# H0BR41.net
KiCad netlist of a schematic drawn in EAGLE
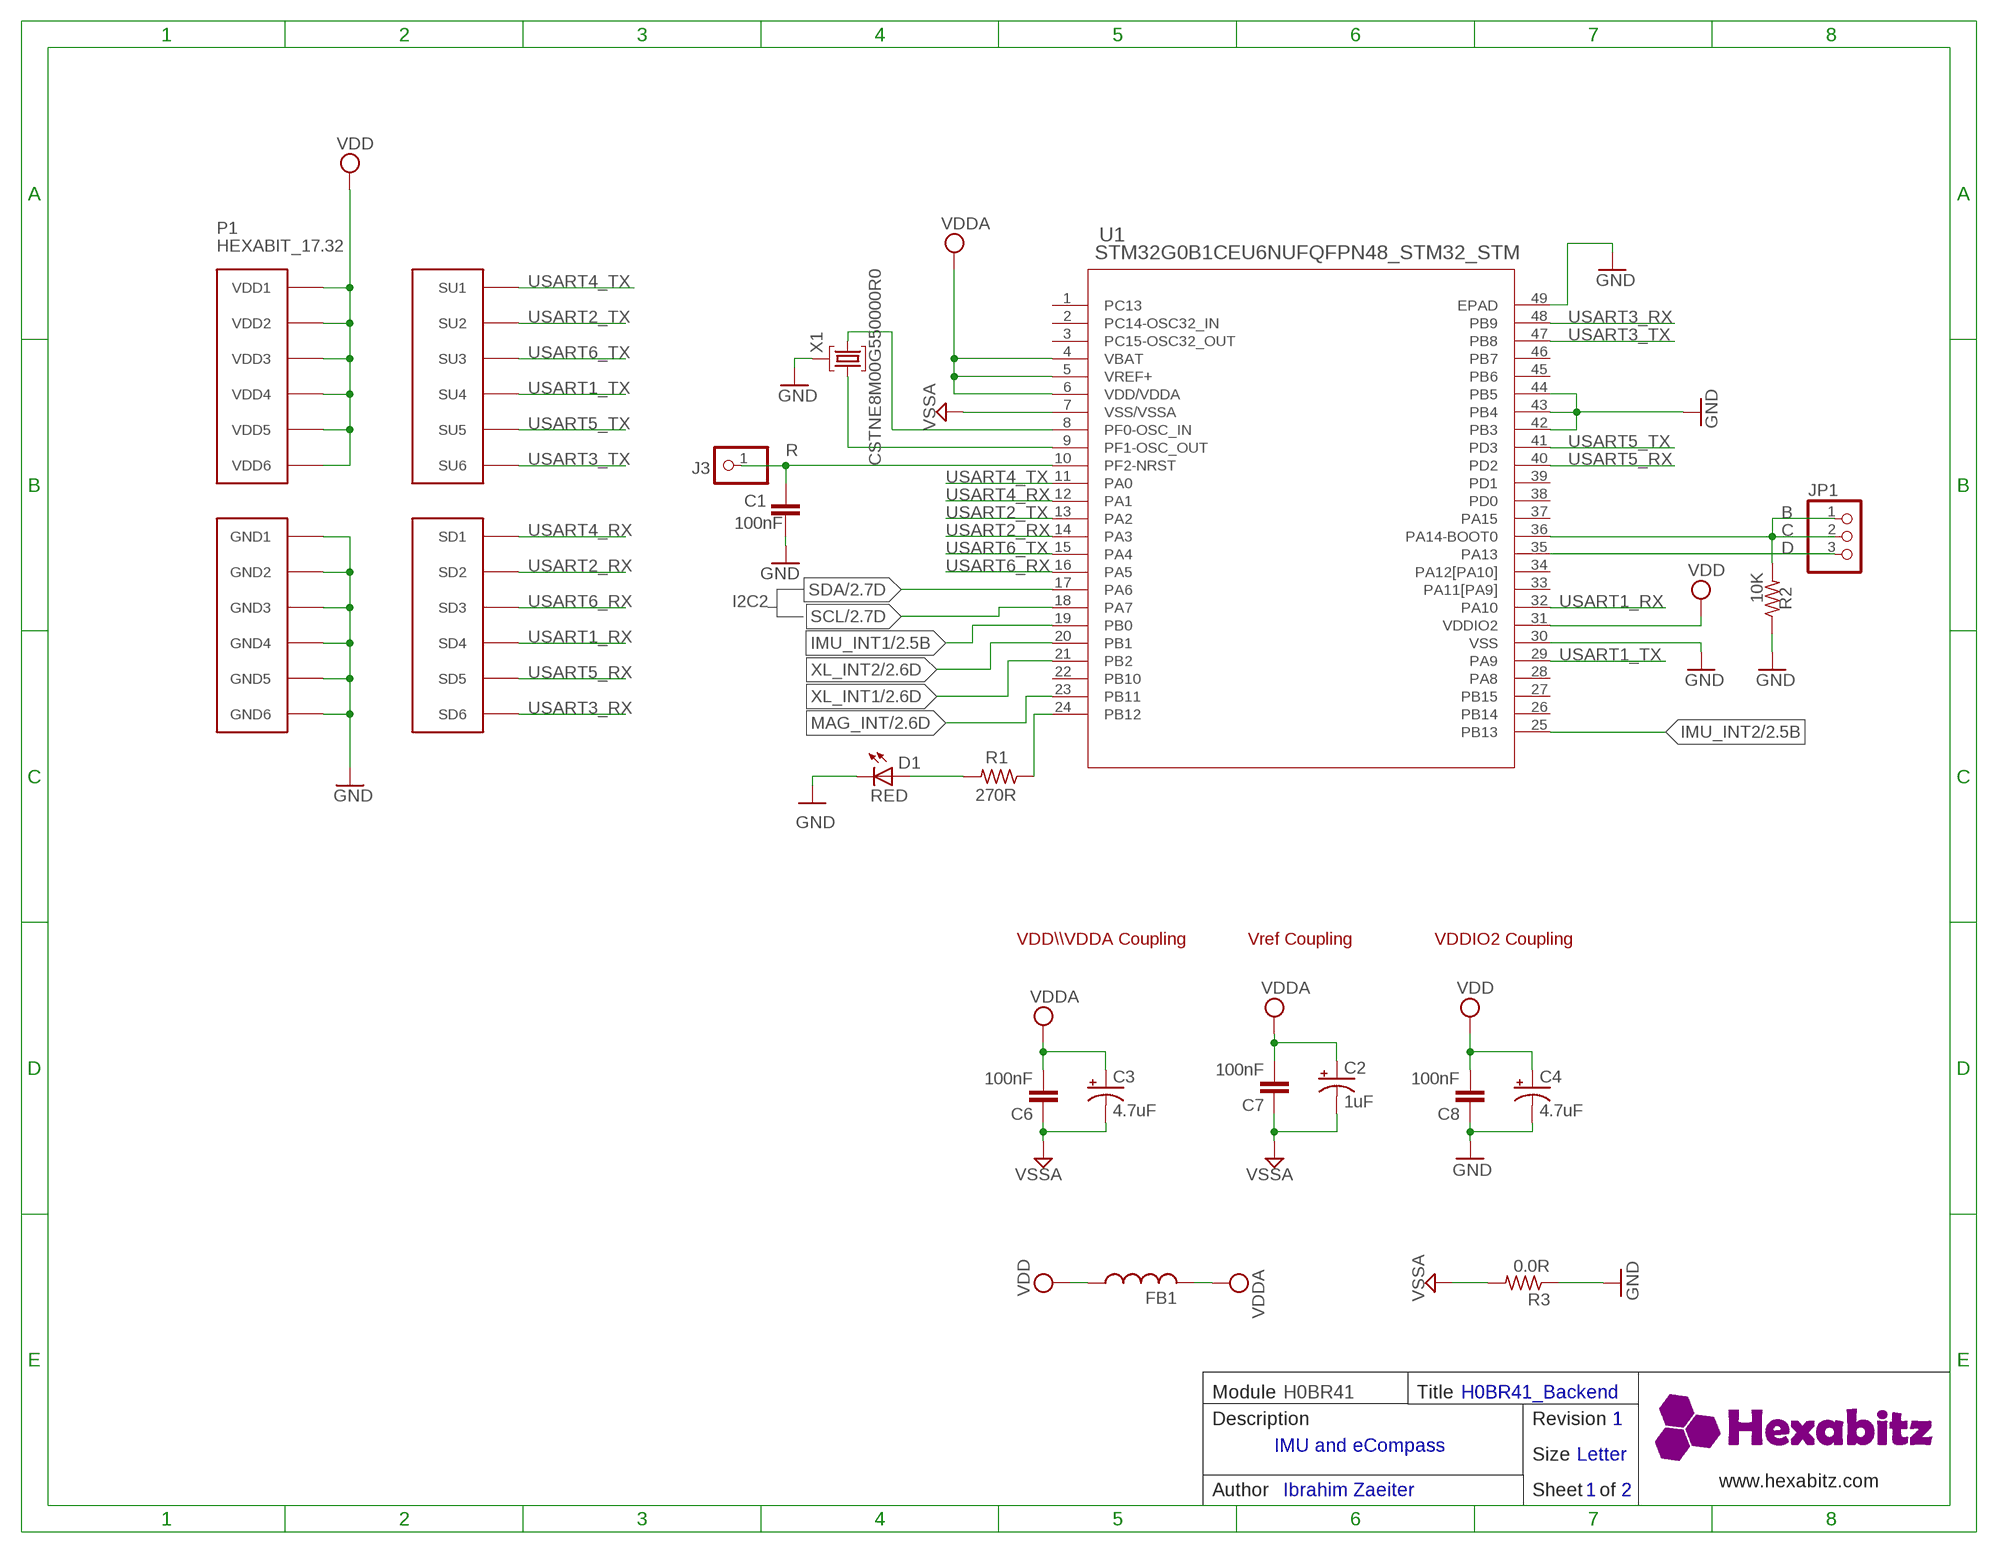
[diagram p0: schematic, sheet 1]
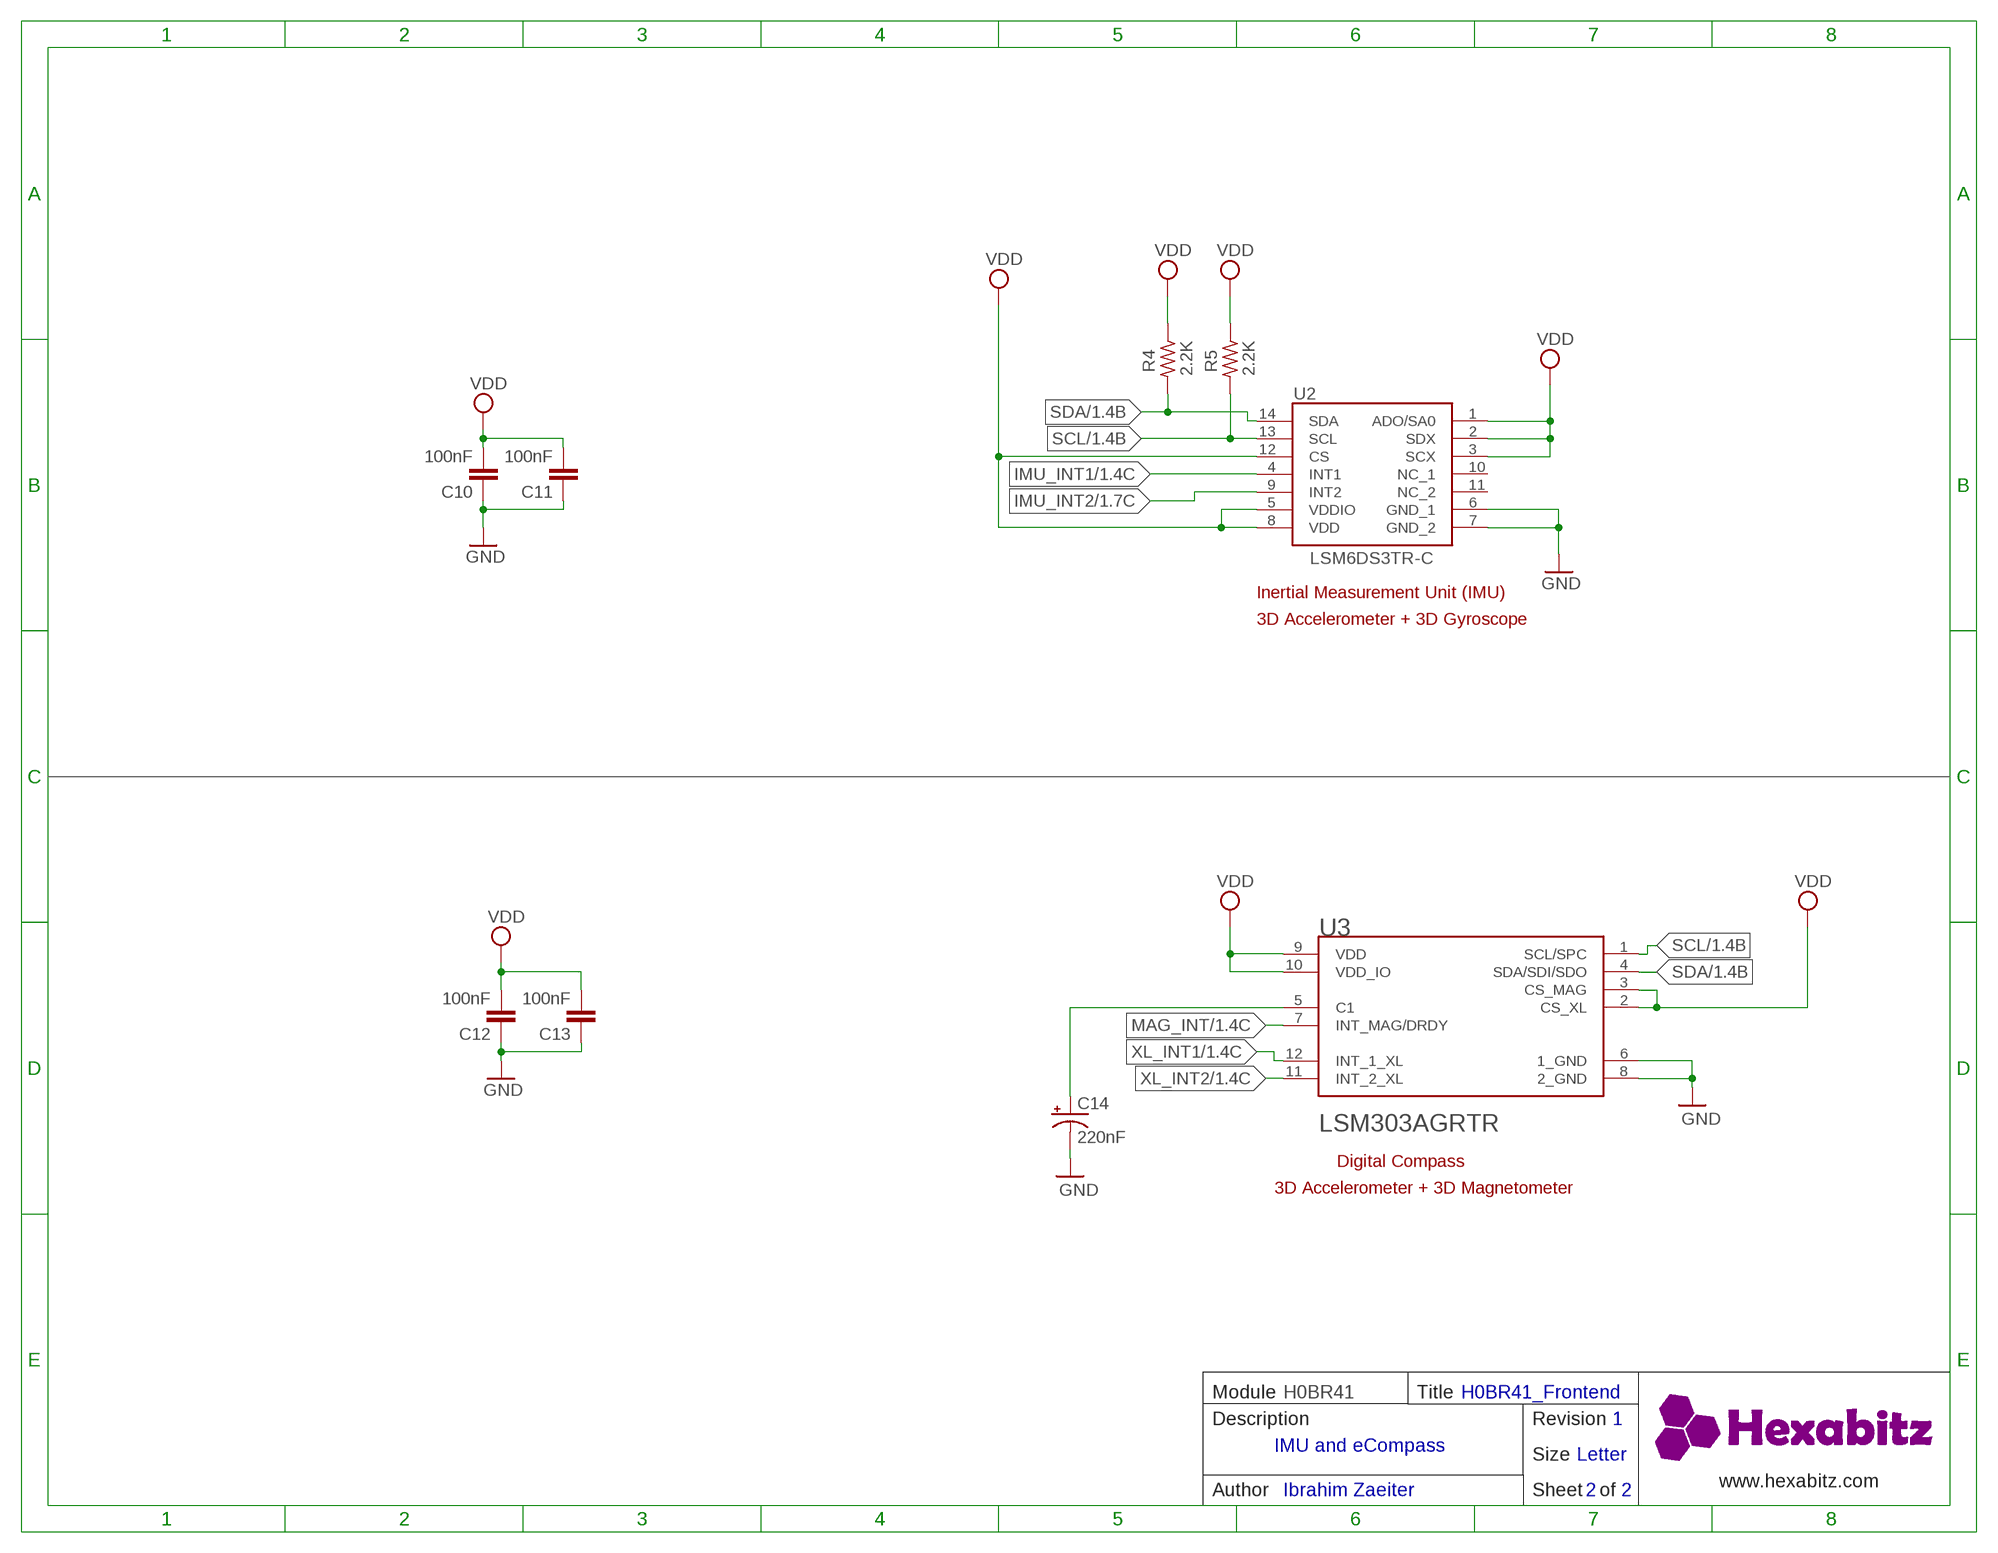
[diagram p1: schematic, sheet 2]

(export (version "E")
  (design (tool "Eeschema 10.0.6"))
  (components
    (comp (ref "C10")
      (value "100nF")
      (footprint "eagle-import:C-0603")
      (fields
        (field (name "CAPACITANCE") "100nF")
        (field (name "MFN") "AVX CORPORATION")
        (field (name "MPN") "'0603YC104K4T2A")
        (field (name "OCTOPART_URL") "'https://octopart.com/0603yc104k4t2a-avx+interconnect+%2F+elco-8120651")
        (field (name "TOLERANCE") "10%")
        (field (name "VOLTAGE_RATING") "16.0 V")
      )
      (libsource (lib "eagle-import") (part "C-0603"))
    )
    (comp (ref "C11")
      (value "100nF")
      (footprint "eagle-import:C-0603")
      (fields
        (field (name "CAPACITANCE") "100nF")
        (field (name "MFN") "AVX CORPORATION")
        (field (name "MPN") "'0603YC104K4T2A")
        (field (name "OCTOPART_URL") "'https://octopart.com/0603yc104k4t2a-avx+interconnect+%2F+elco-8120651")
        (field (name "TOLERANCE") "10%")
        (field (name "VOLTAGE_RATING") "16.0 V")
      )
      (libsource (lib "eagle-import") (part "C-0603"))
    )
    (comp (ref "C12")
      (value "100nF")
      (footprint "eagle-import:C-0603")
      (fields
        (field (name "CAPACITANCE") "100nF")
        (field (name "MFN") "AVX CORPORATION")
        (field (name "MPN") "'0603YC104K4T2A")
        (field (name "OCTOPART_URL") "'https://octopart.com/0603yc104k4t2a-avx+interconnect+%2F+elco-8120651")
        (field (name "TOLERANCE") "10%")
        (field (name "VOLTAGE_RATING") "16.0 V")
      )
      (libsource (lib "eagle-import") (part "C-0603"))
    )
    (comp (ref "C13")
      (value "100nF")
      (footprint "eagle-import:C-0603")
      (fields
        (field (name "CAPACITANCE") "100nF")
        (field (name "MFN") "AVX CORPORATION")
        (field (name "MPN") "'0603YC104K4T2A")
        (field (name "OCTOPART_URL") "'https://octopart.com/0603yc104k4t2a-avx+interconnect+%2F+elco-8120651")
        (field (name "TOLERANCE") "10%")
        (field (name "VOLTAGE_RATING") "16.0 V")
      )
      (libsource (lib "eagle-import") (part "C-0603"))
    )
    (comp (ref "C14")
      (value "220nF")
      (footprint "eagle-import:C-0805-POL")
      (fields
        (field (name "CAPACITANCE") "4.7uF")
        (field (name "MFN") "KEMET ")
        (field (name "MPN") "C0805C224K1RACTU")
        (field (name "OCTOPART_URL") "https://octopart.com/c0805c224k1ractu-kemet-12818106?r=sp")
        (field (name "TOLERANCE") "20%")
        (field (name "VOLTAGE_RATING") "10.0 V")
      )
      (libsource (lib "eagle-import") (part "C-0805-POL"))
    )
    (comp (ref "R4")
      (value "2.2K")
      (footprint "eagle-import:R-0603")
      (fields
        (field (name "MFN") "Yageo")
        (field (name "MPN") "RC0603FR-072K2L")
        (field (name "OCTOPART_URL") "https://octopart.com/rc0603fr-072k2l-yageo-1214512?r=sp")
        (field (name "RESISTANCE") "2.2K Ohm")
        (field (name "TOLERANCE") "5%")
      )
      (libsource (lib "eagle-import") (part "R-0603"))
    )
    (comp (ref "R5")
      (value "2.2K")
      (footprint "eagle-import:R-0603")
      (fields
        (field (name "MFN") "Yageo")
        (field (name "MPN") "RC0603FR-072K2L")
        (field (name "OCTOPART_URL") "https://octopart.com/rc0603fr-072k2l-yageo-1214512?r=sp")
        (field (name "RESISTANCE") "2.2K Ohm")
        (field (name "TOLERANCE") "5%")
      )
      (libsource (lib "eagle-import") (part "R-0603"))
    )
    (comp (ref "U2")
      (value "LSM6DS3TR-C")
      (footprint "eagle-import:LGA-14(2.5X3X0.86)")
      (libsource (lib "eagle-import") (part "LSM6DS3TR-C"))
    )
    (comp (ref "U3")
      (value "STMICROELECTRONICS_LSM303AGRTRSTMICROELECTRONICS_LSM303AGRTR_0_0")
      (footprint "eagle-import:STMICROELECTRONICS_LSM303AGRTR_0")
      (fields
        (field (name "DIGIKEY_PART_NUMBER") "497-16527-1-ND")
        (field (name "MOUSER_PART_NUMBER") "511-LSM303AGRTR")
        (field (name "MPN") "LSM303AGRTR")
      )
      (libsource (lib "eagle-import") (part "STMICROELECTRONICS_LSM303AGRTRSTMICROELECTRONICS_LSM303AGRTR_0_0"))
    )
    (comp (ref "C1")
      (value "100nF")
      (footprint "eagle-import:C-0603")
      (fields
        (field (name "CAPACITANCE") "100nF")
        (field (name "MFN") "AVX CORPORATION")
        (field (name "MPN") "'0603YC104K4T2A")
        (field (name "OCTOPART_URL") "'https://octopart.com/0603yc104k4t2a-avx+interconnect+%2F+elco-8120651")
        (field (name "TOLERANCE") "10%")
        (field (name "VOLTAGE_RATING") "16.0 V")
      )
      (libsource (lib "eagle-import") (part "C-0603"))
    )
    (comp (ref "C2")
      (value "1uF")
      (footprint "eagle-import:C-0805-POL")
      (fields
        (field (name "CAPACITANCE") "1.00uF")
        (field (name "MFN") "'YAGEO [VA]")
        (field (name "MPN") "'CC0805KKX7R7BB105")
        (field (name "OCTOPART_URL") "https://octopart.com/cc0805kkx7r7bb105-yageo-8376555?r=sp")
        (field (name "TOLERANCE") "10%")
        (field (name "VOLTAGE_RATING") "16.0 V")
      )
      (libsource (lib "eagle-import") (part "C-0805-POL"))
    )
    (comp (ref "C3")
      (value "4.7uF")
      (footprint "eagle-import:C-0805-POL")
      (fields
        (field (name "CAPACITANCE") "4.7uF")
        (field (name "MFN") "Panasonic")
        (field (name "MPN") "10TPU4R7MSI")
        (field (name "OCTOPART_URL") "https://octopart.com/10tpu4r7msi-panasonic-29487748")
        (field (name "TOLERANCE") "20%")
        (field (name "VOLTAGE_RATING") "10.0 V")
      )
      (libsource (lib "eagle-import") (part "C-0805-POL"))
    )
    (comp (ref "C4")
      (value "4.7uF")
      (footprint "eagle-import:C-0805-POL")
      (fields
        (field (name "CAPACITANCE") "4.7uF")
        (field (name "MFN") "Panasonic")
        (field (name "MPN") "10TPU4R7MSI")
        (field (name "OCTOPART_URL") "https://octopart.com/10tpu4r7msi-panasonic-29487748")
        (field (name "TOLERANCE") "20%")
        (field (name "VOLTAGE_RATING") "10.0 V")
      )
      (libsource (lib "eagle-import") (part "C-0805-POL"))
    )
    (comp (ref "C6")
      (value "100nF")
      (footprint "eagle-import:C-0603")
      (fields
        (field (name "CAPACITANCE") "100nF")
        (field (name "MFN") "AVX CORPORATION")
        (field (name "MPN") "'0603YC104K4T2A")
        (field (name "OCTOPART_URL") "'https://octopart.com/0603yc104k4t2a-avx+interconnect+%2F+elco-8120651")
        (field (name "TOLERANCE") "10%")
        (field (name "VOLTAGE_RATING") "16.0 V")
      )
      (libsource (lib "eagle-import") (part "C-0603"))
    )
    (comp (ref "C7")
      (value "100nF")
      (footprint "eagle-import:C-0603")
      (fields
        (field (name "CAPACITANCE") "100nF")
        (field (name "MFN") "AVX CORPORATION")
        (field (name "MPN") "'0603YC104K4T2A")
        (field (name "OCTOPART_URL") "'https://octopart.com/0603yc104k4t2a-avx+interconnect+%2F+elco-8120651")
        (field (name "TOLERANCE") "10%")
        (field (name "VOLTAGE_RATING") "16.0 V")
      )
      (libsource (lib "eagle-import") (part "C-0603"))
    )
    (comp (ref "C8")
      (value "100nF")
      (footprint "eagle-import:C-0603")
      (fields
        (field (name "CAPACITANCE") "100nF")
        (field (name "MFN") "AVX CORPORATION")
        (field (name "MPN") "'0603YC104K4T2A")
        (field (name "OCTOPART_URL") "'https://octopart.com/0603yc104k4t2a-avx+interconnect+%2F+elco-8120651")
        (field (name "TOLERANCE") "10%")
        (field (name "VOLTAGE_RATING") "16.0 V")
      )
      (libsource (lib "eagle-import") (part "C-0603"))
    )
    (comp (ref "D1")
      (value "RED")
      (footprint "eagle-import:VLMS1300-GS08")
      (fields (field (name "MPN") "VLMS1300-GS08"))
      (libsource (lib "eagle-import") (part "VLMS1300-GS08"))
    )
    (comp (ref "FB1")
      (value "FB-TDK_MMZ1608Y300B")
      (footprint "eagle-import:FB-TDK_MMZ1608Y300B")
      (fields
        (field (name "MFN") "TDK ")
        (field (name "MPN") "MMZ1608Y300BTA00")
        (field (name "OCTOPART_URL") "https://octopart.com/mmz1608y300bta00-tdk-7906990?r=sp")
      )
      (libsource (lib "eagle-import") (part "FB-TDK_MMZ1608Y300B"))
    )
    (comp (ref "J3")
      (value "PINHD-1X1")
      (footprint "eagle-import:1X01")
      (fields (field (name "MPN") "87227-1"))
      (libsource (lib "eagle-import") (part "PINHD-1X1"))
    )
    (comp (ref "JP1")
      (value "PINHD-1X3")
      (footprint "eagle-import:1X03")
      (libsource (lib "eagle-import") (part "PINHD-1X3"))
    )
    (comp (ref "P1")
      (value "HEXABIT_17.32")
      (footprint "eagle-import:HEXABIT_17.32")
      (libsource (lib "eagle-import") (part "HEXABIT_?17.32"))
    )
    (comp (ref "R1")
      (value "270R")
      (footprint "eagle-import:R-0603")
      (fields
        (field (name "MFN") "'Panasonic")
        (field (name "MPN") "'ERJ-3GEYJ271V")
        (field (name "OCTOPART_URL") "https://octopart.com/erj-3geyj271v-panasonic-55560546?r=sp")
        (field (name "RESISTANCE") "270R")
      )
      (libsource (lib "eagle-import") (part "R-0603"))
    )
    (comp (ref "R2")
      (value "10K")
      (footprint "eagle-import:R-0603")
      (fields
        (field (name "MFN") "Vishay")
        (field (name "MPN") "'060300J0103T5E")
        (field (name "OCTOPART_URL") "https://octopart.com/search?q=060300J0103T5E&currency=USD&specs=0")
        (field (name "RESISTANCE") "10K")
      )
      (libsource (lib "eagle-import") (part "R-0603"))
    )
    (comp (ref "R3")
      (value "0.0R")
      (footprint "eagle-import:R-0603")
      (fields
        (field (name "MFN") "YAGEO [VR]")
        (field (name "MPN") "RC0603JR-070RL")
        (field (name "OCTOPART_URL") "https://octopart.com/rc0603jr-070rl-yageo-1241539?r=sp")
        (field (name "RESISTANCE") "0R")
      )
      (libsource (lib "eagle-import") (part "R-0603"))
    )
    (comp (ref "U1")
      (value "STM32G0B1CEU6NUFQFPN48_STM32_STM")
      (footprint "eagle-import:UFQFPN48_STM32_STM")
      (fields
        (field (name "MPN") "STM32G0B1CEU6N")
        (field (name "COPYRIGHT") "Copyright (C) 2022 Ultra Librarian. All rights reserved.")
      )
      (libsource (lib "eagle-import") (part "STM32G0B1CEU6NUFQFPN48_STM32_STM"))
    )
    (comp (ref "X1")
      (value "CSTNE8M00G550000R0")
      (footprint "eagle-import:XTALL_CSTCE8M00G52")
      (fields
        (field (name "MPN") "CSTCE8M00G52Z-R0")
        (field (name "MPN_1") "CSTNE8M00G550000R0")
        (field (name "OCTOPART_URL") "https://octopart.com/cstne8m00g550000r0-murata-91406934?r=sp")
      )
      (libsource (lib "eagle-import") (part "XTALL_CSTCE8M00G52"))
    )
  )
  (nets
    (net (code "1") (name "C") (class "Default")
      (node (ref "JP1") (pin "1") (pinfunction "1_1") (pintype "passive"))
      (node (ref "JP1") (pin "2") (pinfunction "2_2") (pintype "passive"))
      (node (ref "R2") (pin "2") (pinfunction "2_2") (pintype "passive"))
      (node (ref "U1") (pin "36") (pinfunction "PA14-BOOT0_36") (pintype "bidirectional"))
    )
    (net (code "2") (name "D") (class "Default")
      (node (ref "JP1") (pin "3") (pinfunction "3_3") (pintype "passive"))
      (node (ref "U1") (pin "35") (pinfunction "PA13_35") (pintype "bidirectional"))
    )
    (net (code "3") (name "GND") (class "Default")
      (node (ref "C1") (pin "1") (pinfunction "1_1") (pintype "passive"))
      (node (ref "C10") (pin "1") (pinfunction "1_1") (pintype "passive"))
      (node (ref "C11") (pin "1") (pinfunction "1_1") (pintype "passive"))
      (node (ref "C12") (pin "1") (pinfunction "1_1") (pintype "passive"))
      (node (ref "C13") (pin "1") (pinfunction "1_1") (pintype "passive"))
      (node (ref "C14") (pin "2") (pinfunction "-_2") (pintype "passive"))
      (node (ref "C4") (pin "2") (pinfunction "-_2") (pintype "passive"))
      (node (ref "C8") (pin "1") (pinfunction "1_1") (pintype "passive"))
      (node (ref "D1") (pin "C") (pinfunction "C_C") (pintype "passive"))
      (node (ref "P1") (pin "PAD_PD10") (pinfunction "GND4_PAD_PD10") (pintype "power_in"))
      (node (ref "P1") (pin "PAD_PD11") (pinfunction "GND5_PAD_PD11") (pintype "power_in"))
      (node (ref "P1") (pin "PAD_PD12") (pinfunction "GND6_PAD_PD12") (pintype "power_in"))
      (node (ref "P1") (pin "PAD_PD7") (pinfunction "GND1_PAD_PD7") (pintype "power_in"))
      (node (ref "P1") (pin "PAD_PD8") (pinfunction "GND2_PAD_PD8") (pintype "power_in"))
      (node (ref "P1") (pin "PAD_PD9") (pinfunction "GND3_PAD_PD9") (pintype "power_in"))
      (node (ref "R2") (pin "1") (pinfunction "1_1") (pintype "passive"))
      (node (ref "R3") (pin "1") (pinfunction "1_1") (pintype "passive"))
      (node (ref "U1") (pin "30") (pinfunction "VSS_30") (pintype "passive"))
      (node (ref "U1") (pin "42") (pinfunction "PB3_42") (pintype "bidirectional"))
      (node (ref "U1") (pin "43") (pinfunction "PB4_43") (pintype "bidirectional"))
      (node (ref "U1") (pin "44") (pinfunction "PB5_44") (pintype "bidirectional"))
      (node (ref "U1") (pin "49") (pinfunction "EPAD_49") (pintype "passive"))
      (node (ref "U2") (pin "6") (pinfunction "GND_1_6") (pintype "bidirectional"))
      (node (ref "U2") (pin "7") (pinfunction "GND_2_7") (pintype "bidirectional"))
      (node (ref "U3") (pin "6") (pinfunction "1_GND_6") (pintype "power_in"))
      (node (ref "U3") (pin "8") (pinfunction "2_GND_8") (pintype "power_in"))
      (node (ref "X1") (pin "P$2") (pinfunction "2_P$2") (pintype "passive"))
    )
    (net (code "4") (name "GND1") (class "Default")
      (node (ref "C2") (pin "2") (pinfunction "-_2") (pintype "passive"))
      (node (ref "C3") (pin "2") (pinfunction "-_2") (pintype "passive"))
      (node (ref "C6") (pin "1") (pinfunction "1_1") (pintype "passive"))
      (node (ref "C7") (pin "1") (pinfunction "1_1") (pintype "passive"))
      (node (ref "R3") (pin "2") (pinfunction "2_2") (pintype "passive"))
      (node (ref "U1") (pin "7") (pinfunction "VSS/VSSA_7") (pintype "passive"))
    )
    (net (code "5") (name "IMU_INT1") (class "Default")
      (node (ref "U1") (pin "19") (pinfunction "PB0_19") (pintype "bidirectional"))
      (node (ref "U2") (pin "4") (pinfunction "INT1_4") (pintype "bidirectional"))
    )
    (net (code "6") (name "IMU_INT2") (class "Default")
      (node (ref "U1") (pin "25") (pinfunction "PB13_25") (pintype "bidirectional"))
      (node (ref "U2") (pin "9") (pinfunction "INT2_9") (pintype "bidirectional"))
    )
    (net (code "7") (name "MAG_INT") (class "Default")
      (node (ref "U1") (pin "23") (pinfunction "PB11_23") (pintype "bidirectional"))
      (node (ref "U3") (pin "7") (pinfunction "INT_MAG/DRDY_7") (pintype "input"))
    )
    (net (code "8") (name "Net-(C14-+)") (class "Default")
      (node (ref "C14") (pin "1") (pinfunction "+_1") (pintype "passive"))
      (node (ref "U3") (pin "5") (pinfunction "C1_5") (pintype "passive"))
    )
    (net (code "9") (name "Net-(D1-PadA)") (class "Default")
      (node (ref "D1") (pin "A") (pinfunction "A_A") (pintype "passive"))
      (node (ref "R1") (pin "2") (pinfunction "2_2") (pintype "passive"))
    )
    (net (code "10") (name "Net-(U1-PB12)") (class "Default")
      (node (ref "R1") (pin "1") (pinfunction "1_1") (pintype "passive"))
      (node (ref "U1") (pin "24") (pinfunction "PB12_24") (pintype "bidirectional"))
    )
    (net (code "11") (name "Net-(U1-PF0-OSC_IN)") (class "Default")
      (node (ref "U1") (pin "8") (pinfunction "PF0-OSC_IN_8") (pintype "bidirectional"))
      (node (ref "X1") (pin "P$1") (pinfunction "1_P$1") (pintype "passive"))
    )
    (net (code "12") (name "Net-(U1-PF1-OSC_OUT)") (class "Default")
      (node (ref "U1") (pin "9") (pinfunction "PF1-OSC_OUT_9") (pintype "bidirectional"))
      (node (ref "X1") (pin "P$3") (pinfunction "3_P$3") (pintype "passive"))
    )
    (net (code "13") (name "R") (class "Default")
      (node (ref "C1") (pin "2") (pinfunction "2_2") (pintype "passive"))
      (node (ref "J3") (pin "1") (pinfunction "1_1") (pintype "passive"))
      (node (ref "U1") (pin "10") (pinfunction "PF2-NRST_10") (pintype "bidirectional"))
    )
    (net (code "14") (name "SCL") (class "Default")
      (node (ref "R5") (pin "2") (pinfunction "2_2") (pintype "passive"))
      (node (ref "U1") (pin "18") (pinfunction "PA7_18") (pintype "bidirectional"))
      (node (ref "U2") (pin "13") (pinfunction "SCL_13") (pintype "bidirectional"))
      (node (ref "U3") (pin "1") (pinfunction "SCL/SPC_1") (pintype "input"))
    )
    (net (code "15") (name "SDA") (class "Default")
      (node (ref "R4") (pin "2") (pinfunction "2_2") (pintype "passive"))
      (node (ref "U1") (pin "17") (pinfunction "PA6_17") (pintype "bidirectional"))
      (node (ref "U2") (pin "14") (pinfunction "SDA_14") (pintype "bidirectional"))
      (node (ref "U3") (pin "4") (pinfunction "SDA/SDI/SDO_4") (pintype "bidirectional"))
    )
    (net (code "16") (name "USART1_RX") (class "Default")
      (node (ref "P1") (pin "PAD_PD4") (pinfunction "SD4_PAD_PD4") (pintype "bidirectional"))
      (node (ref "U1") (pin "32") (pinfunction "PA10_32") (pintype "bidirectional"))
    )
    (net (code "17") (name "USART1_TX") (class "Default")
      (node (ref "P1") (pin "PAD_PU4") (pinfunction "SU4_PAD_PU4") (pintype "bidirectional"))
      (node (ref "U1") (pin "29") (pinfunction "PA9_29") (pintype "bidirectional"))
    )
    (net (code "18") (name "USART2_RX") (class "Default")
      (node (ref "P1") (pin "PAD_PD2") (pinfunction "SD2_PAD_PD2") (pintype "bidirectional"))
      (node (ref "U1") (pin "14") (pinfunction "PA3_14") (pintype "bidirectional"))
    )
    (net (code "19") (name "USART2_TX") (class "Default")
      (node (ref "P1") (pin "PAD_PU2") (pinfunction "SU2_PAD_PU2") (pintype "bidirectional"))
      (node (ref "U1") (pin "13") (pinfunction "PA2_13") (pintype "bidirectional"))
    )
    (net (code "20") (name "USART3_RX") (class "Default")
      (node (ref "P1") (pin "PAD_PD6") (pinfunction "SD6_PAD_PD6") (pintype "bidirectional"))
      (node (ref "U1") (pin "48") (pinfunction "PB9_48") (pintype "bidirectional"))
    )
    (net (code "21") (name "USART3_TX") (class "Default")
      (node (ref "P1") (pin "PAD_PU6") (pinfunction "SU6_PAD_PU6") (pintype "bidirectional"))
      (node (ref "U1") (pin "47") (pinfunction "PB8_47") (pintype "bidirectional"))
    )
    (net (code "22") (name "USART4_RX") (class "Default")
      (node (ref "P1") (pin "PAD_PD1") (pinfunction "SD1_PAD_PD1") (pintype "bidirectional"))
      (node (ref "U1") (pin "12") (pinfunction "PA1_12") (pintype "bidirectional"))
    )
    (net (code "23") (name "USART4_TX") (class "Default")
      (node (ref "P1") (pin "PAD_PU1") (pinfunction "SU1_PAD_PU1") (pintype "bidirectional"))
      (node (ref "U1") (pin "11") (pinfunction "PA0_11") (pintype "bidirectional"))
    )
    (net (code "24") (name "USART5_RX") (class "Default")
      (node (ref "P1") (pin "PAD_PD5") (pinfunction "SD5_PAD_PD5") (pintype "bidirectional"))
      (node (ref "U1") (pin "40") (pinfunction "PD2_40") (pintype "bidirectional"))
    )
    (net (code "25") (name "USART5_TX") (class "Default")
      (node (ref "P1") (pin "PAD_PU5") (pinfunction "SU5_PAD_PU5") (pintype "bidirectional"))
      (node (ref "U1") (pin "41") (pinfunction "PD3_41") (pintype "bidirectional"))
    )
    (net (code "26") (name "USART6_RX") (class "Default")
      (node (ref "P1") (pin "PAD_PD3") (pinfunction "SD3_PAD_PD3") (pintype "bidirectional"))
      (node (ref "U1") (pin "16") (pinfunction "PA5_16") (pintype "bidirectional"))
    )
    (net (code "27") (name "USART6_TX") (class "Default")
      (node (ref "P1") (pin "PAD_PU3") (pinfunction "SU3_PAD_PU3") (pintype "bidirectional"))
      (node (ref "U1") (pin "15") (pinfunction "PA4_15") (pintype "bidirectional"))
    )
    (net (code "28") (name "VCC") (class "Default")
      (node (ref "C2") (pin "1") (pinfunction "+_1") (pintype "passive"))
      (node (ref "C3") (pin "1") (pinfunction "+_1") (pintype "passive"))
      (node (ref "C6") (pin "2") (pinfunction "2_2") (pintype "passive"))
      (node (ref "C7") (pin "2") (pinfunction "2_2") (pintype "passive"))
      (node (ref "FB1") (pin "2") (pinfunction "2_2") (pintype "passive"))
      (node (ref "U1") (pin "4") (pinfunction "VBAT_4") (pintype "power_in"))
      (node (ref "U1") (pin "5") (pinfunction "VREF+_5") (pintype "power_in"))
      (node (ref "U1") (pin "6") (pinfunction "VDD/VDDA_6") (pintype "power_in"))
    )
    (net (code "29") (name "VDD") (class "Default")
      (node (ref "C10") (pin "2") (pinfunction "2_2") (pintype "passive"))
      (node (ref "C11") (pin "2") (pinfunction "2_2") (pintype "passive"))
      (node (ref "C12") (pin "2") (pinfunction "2_2") (pintype "passive"))
      (node (ref "C13") (pin "2") (pinfunction "2_2") (pintype "passive"))
      (node (ref "C4") (pin "1") (pinfunction "+_1") (pintype "passive"))
      (node (ref "C8") (pin "2") (pinfunction "2_2") (pintype "passive"))
      (node (ref "FB1") (pin "1") (pinfunction "1_1") (pintype "passive"))
      (node (ref "P1") (pin "PAD_PU10") (pinfunction "VDD4_PAD_PU10") (pintype "power_in"))
      (node (ref "P1") (pin "PAD_PU11") (pinfunction "VDD5_PAD_PU11") (pintype "power_in"))
      (node (ref "P1") (pin "PAD_PU12") (pinfunction "VDD6_PAD_PU12") (pintype "power_in"))
      (node (ref "P1") (pin "PAD_PU7") (pinfunction "VDD1_PAD_PU7") (pintype "power_in"))
      (node (ref "P1") (pin "PAD_PU8") (pinfunction "VDD2_PAD_PU8") (pintype "power_in"))
      (node (ref "P1") (pin "PAD_PU9") (pinfunction "VDD3_PAD_PU9") (pintype "power_in"))
      (node (ref "R4") (pin "1") (pinfunction "1_1") (pintype "passive"))
      (node (ref "R5") (pin "1") (pinfunction "1_1") (pintype "passive"))
      (node (ref "U1") (pin "31") (pinfunction "VDDIO2_31") (pintype "power_in"))
      (node (ref "U2") (pin "1") (pinfunction "ADO/SA0_1") (pintype "bidirectional"))
      (node (ref "U2") (pin "12") (pinfunction "CS_12") (pintype "bidirectional"))
      (node (ref "U2") (pin "2") (pinfunction "SDX_2") (pintype "bidirectional"))
      (node (ref "U2") (pin "3") (pinfunction "SCX_3") (pintype "bidirectional"))
      (node (ref "U2") (pin "5") (pinfunction "VDDIO_5") (pintype "bidirectional"))
      (node (ref "U2") (pin "8") (pinfunction "VDD_8") (pintype "bidirectional"))
      (node (ref "U3") (pin "10") (pinfunction "VDD_IO_10") (pintype "power_in"))
      (node (ref "U3") (pin "2") (pinfunction "CS_XL_2") (pintype "input"))
      (node (ref "U3") (pin "3") (pinfunction "CS_MAG_3") (pintype "input"))
      (node (ref "U3") (pin "9") (pinfunction "VDD_9") (pintype "power_in"))
    )
    (net (code "30") (name "XL_INT1") (class "Default")
      (node (ref "U1") (pin "21") (pinfunction "PB2_21") (pintype "bidirectional"))
      (node (ref "U3") (pin "12") (pinfunction "INT_1_XL_12") (pintype "input"))
    )
    (net (code "31") (name "XL_INT2") (class "Default")
      (node (ref "U1") (pin "20") (pinfunction "PB1_20") (pintype "bidirectional"))
      (node (ref "U3") (pin "11") (pinfunction "INT_2_XL_11") (pintype "input"))
    )
    (net (code "32") (name "unconnected-(U1-PA8-Pad28)") (class "Default")
      (node (ref "U1") (pin "28") (pinfunction "PA8_28") (pintype "bidirectional"))
    )
    (net (code "33") (name "unconnected-(U1-PA11[PA9]-Pad33)") (class "Default")
      (node (ref "U1") (pin "33") (pinfunction "PA11[PA9]_33") (pintype "bidirectional"))
    )
    (net (code "34") (name "unconnected-(U1-PA12[PA10]-Pad34)") (class "Default")
      (node (ref "U1") (pin "34") (pinfunction "PA12[PA10]_34") (pintype "bidirectional"))
    )
    (net (code "35") (name "unconnected-(U1-PA15-Pad37)") (class "Default")
      (node (ref "U1") (pin "37") (pinfunction "PA15_37") (pintype "bidirectional"))
    )
    (net (code "36") (name "unconnected-(U1-PB6-Pad45)") (class "Default")
      (node (ref "U1") (pin "45") (pinfunction "PB6_45") (pintype "bidirectional"))
    )
    (net (code "37") (name "unconnected-(U1-PB7-Pad46)") (class "Default")
      (node (ref "U1") (pin "46") (pinfunction "PB7_46") (pintype "bidirectional"))
    )
    (net (code "38") (name "unconnected-(U1-PB10-Pad22)") (class "Default")
      (node (ref "U1") (pin "22") (pinfunction "PB10_22") (pintype "bidirectional"))
    )
    (net (code "39") (name "unconnected-(U1-PB14-Pad26)") (class "Default")
      (node (ref "U1") (pin "26") (pinfunction "PB14_26") (pintype "bidirectional"))
    )
    (net (code "40") (name "unconnected-(U1-PB15-Pad27)") (class "Default")
      (node (ref "U1") (pin "27") (pinfunction "PB15_27") (pintype "bidirectional"))
    )
    (net (code "41") (name "unconnected-(U1-PC13-Pad1)") (class "Default")
      (node (ref "U1") (pin "1") (pinfunction "PC13_1") (pintype "bidirectional"))
    )
    (net (code "42") (name "unconnected-(U1-PC14-OSC32_IN-Pad2)") (class "Default")
      (node (ref "U1") (pin "2") (pinfunction "PC14-OSC32_IN_2") (pintype "bidirectional"))
    )
    (net (code "43") (name "unconnected-(U1-PC15-OSC32_OUT-Pad3)") (class "Default")
      (node (ref "U1") (pin "3") (pinfunction "PC15-OSC32_OUT_3") (pintype "bidirectional"))
    )
    (net (code "44") (name "unconnected-(U1-PD0-Pad38)") (class "Default")
      (node (ref "U1") (pin "38") (pinfunction "PD0_38") (pintype "bidirectional"))
    )
    (net (code "45") (name "unconnected-(U1-PD1-Pad39)") (class "Default")
      (node (ref "U1") (pin "39") (pinfunction "PD1_39") (pintype "bidirectional"))
    )
    (net (code "46") (name "unconnected-(U2-NC_1-Pad10)") (class "Default")
      (node (ref "U2") (pin "10") (pinfunction "NC_1_10") (pintype "bidirectional"))
    )
    (net (code "47") (name "unconnected-(U2-NC_2-Pad11)") (class "Default")
      (node (ref "U2") (pin "11") (pinfunction "NC_2_11") (pintype "bidirectional"))
    )
  )
)
